# STM32F1_CNC_SCHB.net
KiCad netlist of a schematic drawn in Altium Designer
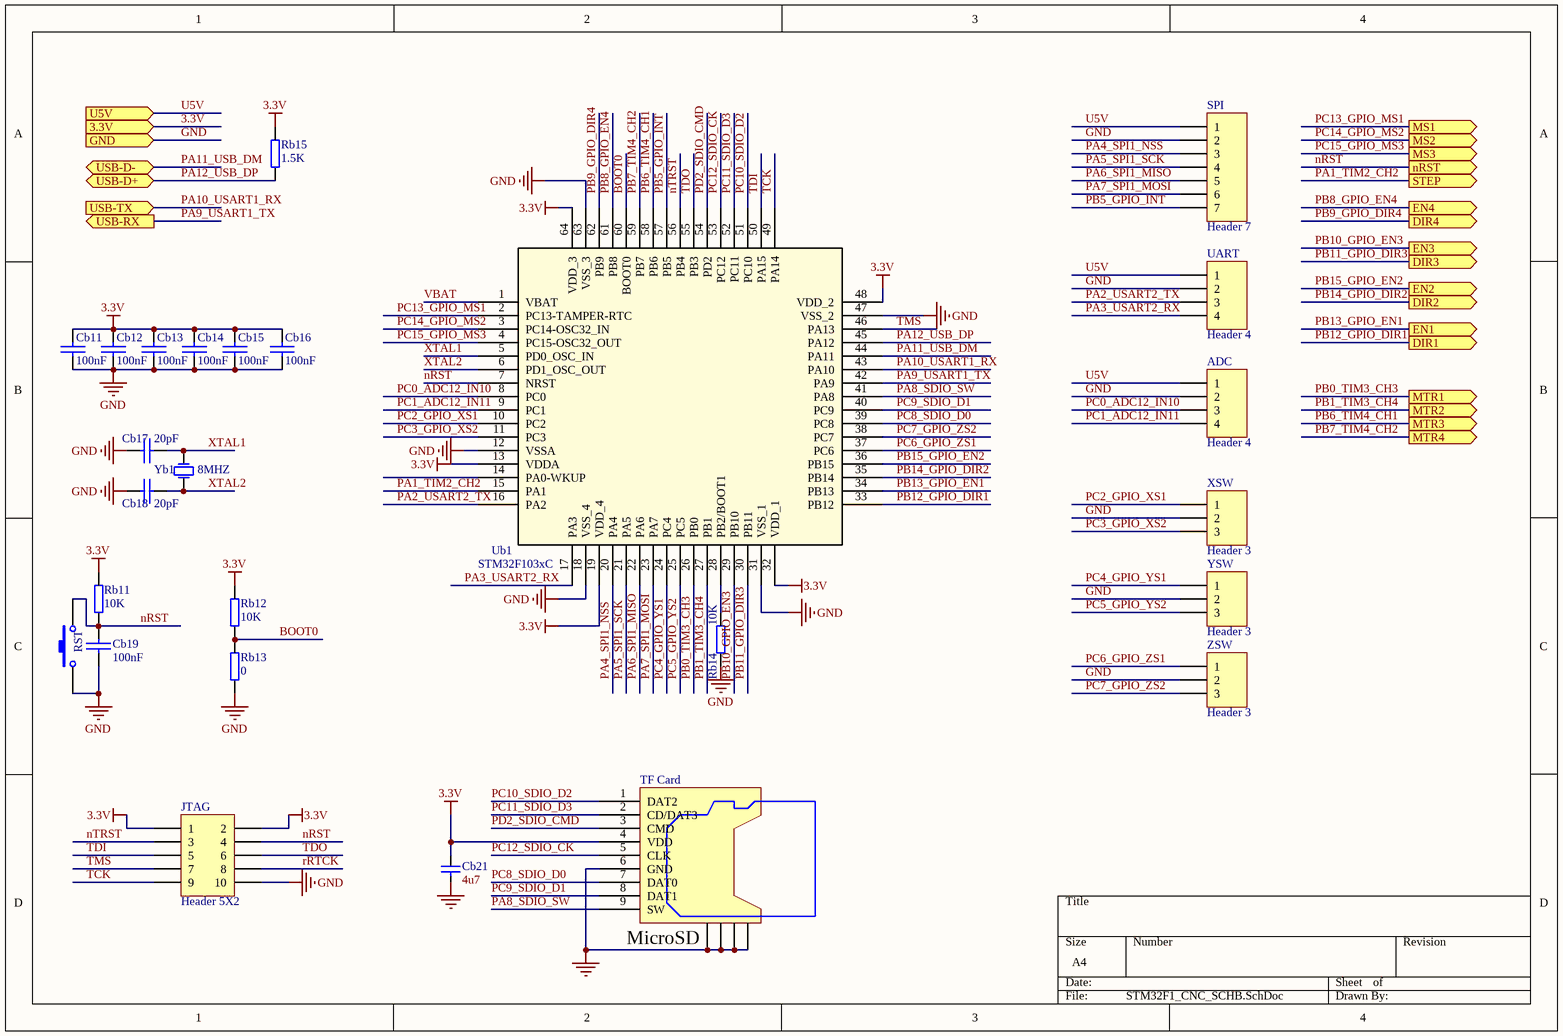
[diagram p0: STM32F1_CNC_SCHB.SchDoc]

(export (version "E")
  (design (tool "Eeschema 10.0.6"))
  (components
    (comp (ref "ADC")
      (value "Header 4")
      (footprint "HDR-2.54-4P")
      (description "Header, 4-Pin")
      (fields (field (name "PUBLISHER") "Altium Limited"))
      (libsource (lib "Miscellaneous Connectors") (part "Header 4"))
    )
    (comp (ref "Cb11")
      (value "100nF")
      (footprint "0603")
      (description "Capacitor")
      (libsource (lib "WEDOLIB") (part "CAP"))
    )
    (comp (ref "Cb12")
      (value "100nF")
      (footprint "0603")
      (description "Capacitor")
      (libsource (lib "WEDOLIB") (part "CAP"))
    )
    (comp (ref "Cb13")
      (value "100nF")
      (footprint "0603")
      (description "Capacitor")
      (libsource (lib "WEDOLIB") (part "CAP"))
    )
    (comp (ref "Cb14")
      (value "100nF")
      (footprint "0603")
      (description "Capacitor")
      (libsource (lib "WEDOLIB") (part "CAP"))
    )
    (comp (ref "Cb15")
      (value "100nF")
      (footprint "0603")
      (description "Capacitor")
      (libsource (lib "WEDOLIB") (part "CAP"))
    )
    (comp (ref "Cb16")
      (value "100nF")
      (footprint "0603")
      (description "Capacitor")
      (libsource (lib "WEDOLIB") (part "CAP"))
    )
    (comp (ref "Cb17")
      (value "20pF")
      (footprint "0603")
      (description "Capacitor")
      (libsource (lib "wedolib") (part "CAP"))
    )
    (comp (ref "Cb18")
      (value "20pF")
      (footprint "0603")
      (description "Capacitor")
      (libsource (lib "wedolib") (part "CAP"))
    )
    (comp (ref "Cb19")
      (value "100nF")
      (footprint "0603")
      (description "Capacitor")
      (libsource (lib "wedolib") (part "CAP"))
    )
    (comp (ref "Cb21") (value "4u7") (footprint "0603") (libsource (lib "s_device") (part "Cap")))
    (comp (ref "JTAG")
      (value "Header 5X2")
      (footprint "IDC10P-2.54")
      (description "Header, 5-Pin, Dual row")
      (fields (field (name "PUBLISHER") "Altium Limited"))
      (libsource (lib "Miscellaneous Connectors") (part "Header 5X2"))
    )
    (comp (ref "Rb11")
      (value "10K")
      (footprint "0603")
      (description "Resister")
      (libsource (lib "wedolib") (part "RES1"))
    )
    (comp (ref "Rb12")
      (value "10K")
      (footprint "0603")
      (description "Resister")
      (libsource (lib "WEDOLIB") (part "RES1"))
    )
    (comp (ref "Rb13")
      (value "0")
      (footprint "0603")
      (description "Resister")
      (libsource (lib "WEDOLIB") (part "RES1"))
    )
    (comp (ref "Rb14")
      (value "10K")
      (footprint "0603")
      (description "Resister")
      (libsource (lib "WEDOLIB") (part "RES1"))
    )
    (comp (ref "Rb15")
      (value "1.5K")
      (footprint "0603")
      (description "Resister")
      (libsource (lib "wedolib") (part "RES1"))
    )
    (comp (ref "RST")
      (value "SW-PB")
      (footprint "RST-6*6")
      (description "Switch")
      (fields (field (name "PUBLISHER") "Altium Limited"))
      (libsource (lib "Miscellaneous Devices") (part "SW-PB"))
    )
    (comp (ref "SPI")
      (value "Header 7")
      (footprint "HDR-2.54-7P")
      (description "Header, 7-Pin")
      (fields (field (name "PUBLISHER") "Altium Limited"))
      (libsource (lib "Miscellaneous Connectors") (part "Header 7"))
    )
    (comp (ref "TF Card")
      (value "microSD PUSH-PULL")
      (footprint "TF Card")
      (libsource (lib "pyboard") (part "microSD PUSH-PULL"))
    )
    (comp (ref "UART")
      (value "Header 4")
      (footprint "HDR-2.54-4P")
      (description "Header, 4-Pin")
      (fields (field (name "PUBLISHER") "Altium Limited"))
      (libsource (lib "Miscellaneous Connectors") (part "Header 4"))
    )
    (comp (ref "Ub1")
      (value "STM32F103xC")
      (footprint "QFP64")
      (libsource (lib "STM32F103xC") (part "STM32F103xC"))
    )
    (comp (ref "XSW")
      (value "Header 3")
      (footprint "HDR-2.54-3P")
      (description "Header, 3-Pin")
      (fields (field (name "PUBLISHER") "Altium Limited"))
      (libsource (lib "Miscellaneous Connectors") (part "Header 3"))
    )
    (comp (ref "Yb1")
      (value "8MHZ")
      (footprint "XTAL-3215-2P")
      (description "Crystal Oscillator")
      (fields (field (name "PUBLISHER") "Altium Limited"))
      (libsource (lib "*") (part "ECS-10-13-1"))
    )
    (comp (ref "YSW")
      (value "Header 3")
      (footprint "HDR-2.54-3P")
      (description "Header, 3-Pin")
      (fields (field (name "PUBLISHER") "Altium Limited"))
      (libsource (lib "Miscellaneous Connectors") (part "Header 3"))
    )
    (comp (ref "ZSW")
      (value "Header 3")
      (footprint "HDR-2.54-3P")
      (description "Header, 3-Pin")
      (fields (field (name "PUBLISHER") "Altium Limited"))
      (libsource (lib "Miscellaneous Connectors") (part "Header 3"))
    )
  )
  (nets
    (net (code "1") (name "/BOOT0") (class "Default")
      (node (ref "Rb12") (pin "2") (pinfunction "2_2") (pintype "passive"))
      (node (ref "Rb13") (pin "1") (pinfunction "1_1") (pintype "passive"))
      (node (ref "Ub1") (pin "60") (pinfunction "BOOT0_60") (pintype "passive"))
    )
    (net (code "2") (name "/PA1_TIM2_CH2") (class "Default")
      (node (ref "Ub1") (pin "15") (pinfunction "PA1_15") (pintype "passive"))
    )
    (net (code "3") (name "/PA2_USART2_TX") (class "Default")
      (node (ref "UART") (pin "3") (pinfunction "3_3") (pintype "passive"))
      (node (ref "Ub1") (pin "16") (pinfunction "PA2_16") (pintype "passive"))
    )
    (net (code "4") (name "/PA3_USART2_RX") (class "Default")
      (node (ref "UART") (pin "4") (pinfunction "4_4") (pintype "passive"))
      (node (ref "Ub1") (pin "17") (pinfunction "PA3_17") (pintype "passive"))
    )
    (net (code "5") (name "/PA4_SPI1_NSS") (class "Default")
      (node (ref "SPI") (pin "3") (pinfunction "3_3") (pintype "passive"))
      (node (ref "Ub1") (pin "20") (pinfunction "PA4_20") (pintype "passive"))
    )
    (net (code "6") (name "/PA5_SPI1_SCK") (class "Default")
      (node (ref "SPI") (pin "4") (pinfunction "4_4") (pintype "passive"))
      (node (ref "Ub1") (pin "21") (pinfunction "PA5_21") (pintype "passive"))
    )
    (net (code "7") (name "/PA6_SPI1_MISO") (class "Default")
      (node (ref "SPI") (pin "5") (pinfunction "5_5") (pintype "passive"))
      (node (ref "Ub1") (pin "22") (pinfunction "PA6_22") (pintype "passive"))
    )
    (net (code "8") (name "/PA7_SPI1_MOSI") (class "Default")
      (node (ref "SPI") (pin "6") (pinfunction "6_6") (pintype "passive"))
      (node (ref "Ub1") (pin "23") (pinfunction "PA7_23") (pintype "passive"))
    )
    (net (code "9") (name "/PA8_SDIO_SW") (class "Default")
      (node (ref "TF Card") (pin "9") (pinfunction "SW_9") (pintype "passive"))
      (node (ref "Ub1") (pin "41") (pinfunction "PA8_41") (pintype "passive"))
    )
    (net (code "10") (name "/PA9_USART1_TX") (class "Default")
      (node (ref "Ub1") (pin "42") (pinfunction "PA9_42") (pintype "passive"))
    )
    (net (code "11") (name "/PA10_USART1_RX") (class "Default")
      (node (ref "Ub1") (pin "43") (pinfunction "PA10_43") (pintype "passive"))
    )
    (net (code "12") (name "/PA11_USB_DM") (class "Default")
      (node (ref "Ub1") (pin "44") (pinfunction "PA11_44") (pintype "passive"))
    )
    (net (code "13") (name "/PA12_USB_DP") (class "Default")
      (node (ref "Rb15") (pin "2") (pinfunction "2_2") (pintype "passive"))
      (node (ref "Ub1") (pin "45") (pinfunction "PA12_45") (pintype "passive"))
    )
    (net (code "14") (name "/PB0_TIM3_CH3") (class "Default")
      (node (ref "Ub1") (pin "26") (pinfunction "PB0_26") (pintype "passive"))
    )
    (net (code "15") (name "/PB1_TIM3_CH4") (class "Default")
      (node (ref "Ub1") (pin "27") (pinfunction "PB1_27") (pintype "passive"))
    )
    (net (code "16") (name "/PB5_GPIO_INT") (class "Default")
      (node (ref "SPI") (pin "7") (pinfunction "7_7") (pintype "passive"))
      (node (ref "Ub1") (pin "57") (pinfunction "PB5_57") (pintype "passive"))
    )
    (net (code "17") (name "/PB6_TIM4_CH1") (class "Default")
      (node (ref "Ub1") (pin "58") (pinfunction "PB6_58") (pintype "passive"))
    )
    (net (code "18") (name "/PB7_TIM4_CH2") (class "Default")
      (node (ref "Ub1") (pin "59") (pinfunction "PB7_59") (pintype "passive"))
    )
    (net (code "19") (name "/PB8_GPIO_EN4") (class "Default")
      (node (ref "Ub1") (pin "61") (pinfunction "PB8_61") (pintype "passive"))
    )
    (net (code "20") (name "/PB9_GPIO_DIR4") (class "Default")
      (node (ref "Ub1") (pin "62") (pinfunction "PB9_62") (pintype "passive"))
    )
    (net (code "21") (name "/PB10_GPIO_EN3") (class "Default")
      (node (ref "Ub1") (pin "29") (pinfunction "PB10_29") (pintype "passive"))
    )
    (net (code "22") (name "/PB11_GPIO_DIR3") (class "Default")
      (node (ref "Ub1") (pin "30") (pinfunction "PB11_30") (pintype "passive"))
    )
    (net (code "23") (name "/PB12_GPIO_DIR1") (class "Default")
      (node (ref "Ub1") (pin "33") (pinfunction "PB12_33") (pintype "passive"))
    )
    (net (code "24") (name "/PB13_GPIO_EN1") (class "Default")
      (node (ref "Ub1") (pin "34") (pinfunction "PB13_34") (pintype "passive"))
    )
    (net (code "25") (name "/PB14_GPIO_DIR2") (class "Default")
      (node (ref "Ub1") (pin "35") (pinfunction "PB14_35") (pintype "passive"))
    )
    (net (code "26") (name "/PB15_GPIO_EN2") (class "Default")
      (node (ref "Ub1") (pin "36") (pinfunction "PB15_36") (pintype "passive"))
    )
    (net (code "27") (name "/PC0_ADC12_IN10") (class "Default")
      (node (ref "ADC") (pin "3") (pinfunction "3_3") (pintype "passive"))
      (node (ref "Ub1") (pin "8") (pinfunction "PC0_8") (pintype "passive"))
    )
    (net (code "28") (name "/PC1_ADC12_IN11") (class "Default")
      (node (ref "ADC") (pin "4") (pinfunction "4_4") (pintype "passive"))
      (node (ref "Ub1") (pin "9") (pinfunction "PC1_9") (pintype "passive"))
    )
    (net (code "29") (name "/PC2_GPIO_XS1") (class "Default")
      (node (ref "Ub1") (pin "10") (pinfunction "PC2_10") (pintype "passive"))
      (node (ref "XSW") (pin "1") (pinfunction "1_1") (pintype "passive"))
    )
    (net (code "30") (name "/PC3_GPIO_XS2") (class "Default")
      (node (ref "Ub1") (pin "11") (pinfunction "PC3_11") (pintype "passive"))
      (node (ref "XSW") (pin "3") (pinfunction "3_3") (pintype "passive"))
    )
    (net (code "31") (name "/PC4_GPIO_YS1") (class "Default")
      (node (ref "Ub1") (pin "24") (pinfunction "PC4_24") (pintype "passive"))
      (node (ref "YSW") (pin "1") (pinfunction "1_1") (pintype "passive"))
    )
    (net (code "32") (name "/PC5_GPIO_YS2") (class "Default")
      (node (ref "Ub1") (pin "25") (pinfunction "PC5_25") (pintype "passive"))
      (node (ref "YSW") (pin "3") (pinfunction "3_3") (pintype "passive"))
    )
    (net (code "33") (name "/PC6_GPIO_ZS1") (class "Default")
      (node (ref "Ub1") (pin "37") (pinfunction "PC6_37") (pintype "passive"))
      (node (ref "ZSW") (pin "1") (pinfunction "1_1") (pintype "passive"))
    )
    (net (code "34") (name "/PC7_GPIO_ZS2") (class "Default")
      (node (ref "Ub1") (pin "38") (pinfunction "PC7_38") (pintype "passive"))
      (node (ref "ZSW") (pin "3") (pinfunction "3_3") (pintype "passive"))
    )
    (net (code "35") (name "/PC8_SDIO_D0") (class "Default")
      (node (ref "TF Card") (pin "7") (pinfunction "DAT0_7") (pintype "passive"))
      (node (ref "Ub1") (pin "39") (pinfunction "PC8_39") (pintype "passive"))
    )
    (net (code "36") (name "/PC9_SDIO_D1") (class "Default")
      (node (ref "TF Card") (pin "8") (pinfunction "DAT1_8") (pintype "passive"))
      (node (ref "Ub1") (pin "40") (pinfunction "PC9_40") (pintype "passive"))
    )
    (net (code "37") (name "/PC10_SDIO_D2") (class "Default")
      (node (ref "TF Card") (pin "1") (pinfunction "DAT2_1") (pintype "passive"))
      (node (ref "Ub1") (pin "51") (pinfunction "PC10_51") (pintype "passive"))
    )
    (net (code "38") (name "/PC11_SDIO_D3") (class "Default")
      (node (ref "TF Card") (pin "2") (pinfunction "CD/DAT3_2") (pintype "passive"))
      (node (ref "Ub1") (pin "52") (pinfunction "PC11_52") (pintype "passive"))
    )
    (net (code "39") (name "/PC12_SDIO_CK") (class "Default")
      (node (ref "TF Card") (pin "5") (pinfunction "CLK_5") (pintype "passive"))
      (node (ref "Ub1") (pin "53") (pinfunction "PC12_53") (pintype "passive"))
    )
    (net (code "40") (name "/PC13_GPIO_MS1") (class "Default")
      (node (ref "Ub1") (pin "2") (pinfunction "PC13-TAMPER-RTC_2") (pintype "passive"))
    )
    (net (code "41") (name "/PC14_GPIO_MS2") (class "Default")
      (node (ref "Ub1") (pin "3") (pinfunction "PC14-OSC32_IN_3") (pintype "passive"))
    )
    (net (code "42") (name "/PC15_GPIO_MS3") (class "Default")
      (node (ref "Ub1") (pin "4") (pinfunction "PC15-OSC32_OUT_4") (pintype "passive"))
    )
    (net (code "43") (name "/PD2_SDIO_CMD") (class "Default")
      (node (ref "TF Card") (pin "3") (pinfunction "CMD_3") (pintype "passive"))
      (node (ref "Ub1") (pin "54") (pinfunction "PD2_54") (pintype "passive"))
    )
    (net (code "44") (name "/TCK") (class "Default")
      (node (ref "JTAG") (pin "9") (pinfunction "9_9") (pintype "passive"))
      (node (ref "Ub1") (pin "49") (pinfunction "PA14_49") (pintype "passive"))
    )
    (net (code "45") (name "/TDI") (class "Default")
      (node (ref "JTAG") (pin "5") (pinfunction "5_5") (pintype "passive"))
      (node (ref "Ub1") (pin "50") (pinfunction "PA15_50") (pintype "passive"))
    )
    (net (code "46") (name "/TDO") (class "Default")
      (node (ref "JTAG") (pin "6") (pinfunction "6_6") (pintype "passive"))
      (node (ref "Ub1") (pin "55") (pinfunction "PB3_55") (pintype "passive"))
    )
    (net (code "47") (name "/TMS") (class "Default")
      (node (ref "JTAG") (pin "7") (pinfunction "7_7") (pintype "passive"))
      (node (ref "Ub1") (pin "46") (pinfunction "PA13_46") (pintype "passive"))
    )
    (net (code "48") (name "/U5V") (class "Default")
      (node (ref "ADC") (pin "1") (pinfunction "1_1") (pintype "passive"))
      (node (ref "SPI") (pin "1") (pinfunction "1_1") (pintype "passive"))
      (node (ref "UART") (pin "1") (pinfunction "1_1") (pintype "passive"))
    )
    (net (code "49") (name "/VBAT") (class "Default")
      (node (ref "Ub1") (pin "1") (pinfunction "VBAT_1") (pintype "passive"))
    )
    (net (code "50") (name "/XTAL1") (class "Default")
      (node (ref "Cb17") (pin "2") (pinfunction "2_2") (pintype "passive"))
      (node (ref "Ub1") (pin "5") (pinfunction "PD0_OSC_IN_5") (pintype "passive"))
      (node (ref "Yb1") (pin "2") (pinfunction "OSC2_2") (pintype "passive"))
    )
    (net (code "51") (name "/XTAL2") (class "Default")
      (node (ref "Cb18") (pin "2") (pinfunction "2_2") (pintype "passive"))
      (node (ref "Ub1") (pin "6") (pinfunction "PD1_OSC_OUT_6") (pintype "passive"))
      (node (ref "Yb1") (pin "1") (pinfunction "OSC1_1") (pintype "passive"))
    )
    (net (code "52") (name "/nRST") (class "Default")
      (node (ref "Cb19") (pin "1") (pinfunction "1_1") (pintype "passive"))
      (node (ref "JTAG") (pin "4") (pinfunction "4_4") (pintype "passive"))
      (node (ref "RST") (pin "1") (pinfunction "1_1") (pintype "passive"))
      (node (ref "Rb11") (pin "2") (pinfunction "2_2") (pintype "passive"))
      (node (ref "Ub1") (pin "7") (pinfunction "NRST_7") (pintype "passive"))
    )
    (net (code "53") (name "/nTRST") (class "Default")
      (node (ref "JTAG") (pin "3") (pinfunction "3_3") (pintype "passive"))
      (node (ref "Ub1") (pin "56") (pinfunction "PB4_56") (pintype "passive"))
    )
    (net (code "54") (name "/rRTCK") (class "Default")
      (node (ref "JTAG") (pin "8") (pinfunction "8_8") (pintype "passive"))
    )
    (net (code "55") (name "3.3V") (class "Default")
      (node (ref "Cb11") (pin "1") (pinfunction "1_1") (pintype "passive"))
      (node (ref "Cb12") (pin "1") (pinfunction "1_1") (pintype "passive"))
      (node (ref "Cb13") (pin "1") (pinfunction "1_1") (pintype "passive"))
      (node (ref "Cb14") (pin "1") (pinfunction "1_1") (pintype "passive"))
      (node (ref "Cb15") (pin "1") (pinfunction "1_1") (pintype "passive"))
      (node (ref "Cb16") (pin "1") (pinfunction "1_1") (pintype "passive"))
      (node (ref "Cb21") (pin "2") (pintype "passive"))
      (node (ref "JTAG") (pin "1") (pinfunction "1_1") (pintype "passive"))
      (node (ref "JTAG") (pin "2") (pinfunction "2_2") (pintype "passive"))
      (node (ref "Rb11") (pin "1") (pinfunction "1_1") (pintype "passive"))
      (node (ref "Rb12") (pin "1") (pinfunction "1_1") (pintype "passive"))
      (node (ref "Rb15") (pin "1") (pinfunction "1_1") (pintype "passive"))
      (node (ref "TF Card") (pin "4") (pinfunction "VDD_4") (pintype "passive"))
      (node (ref "Ub1") (pin "13") (pinfunction "VDDA_13") (pintype "passive"))
      (node (ref "Ub1") (pin "19") (pinfunction "VDD_4_19") (pintype "passive"))
      (node (ref "Ub1") (pin "32") (pinfunction "VDD_1_32") (pintype "passive"))
      (node (ref "Ub1") (pin "48") (pinfunction "VDD_2_48") (pintype "passive"))
      (node (ref "Ub1") (pin "64") (pinfunction "VDD_3_64") (pintype "passive"))
    )
    (net (code "56") (name "GND") (class "Default")
      (node (ref "ADC") (pin "2") (pinfunction "2_2") (pintype "passive"))
      (node (ref "Cb11") (pin "2") (pinfunction "2_2") (pintype "passive"))
      (node (ref "Cb12") (pin "2") (pinfunction "2_2") (pintype "passive"))
      (node (ref "Cb13") (pin "2") (pinfunction "2_2") (pintype "passive"))
      (node (ref "Cb14") (pin "2") (pinfunction "2_2") (pintype "passive"))
      (node (ref "Cb15") (pin "2") (pinfunction "2_2") (pintype "passive"))
      (node (ref "Cb16") (pin "2") (pinfunction "2_2") (pintype "passive"))
      (node (ref "Cb17") (pin "1") (pinfunction "1_1") (pintype "passive"))
      (node (ref "Cb18") (pin "1") (pinfunction "1_1") (pintype "passive"))
      (node (ref "Cb19") (pin "2") (pinfunction "2_2") (pintype "passive"))
      (node (ref "Cb21") (pin "1") (pintype "passive"))
      (node (ref "JTAG") (pin "10") (pinfunction "10_10") (pintype "passive"))
      (node (ref "RST") (pin "2") (pinfunction "2_2") (pintype "passive"))
      (node (ref "Rb13") (pin "2") (pinfunction "2_2") (pintype "passive"))
      (node (ref "Rb14") (pin "2") (pinfunction "2_2") (pintype "passive"))
      (node (ref "SPI") (pin "2") (pinfunction "2_2") (pintype "passive"))
      (node (ref "TF Card") (pin "6") (pinfunction "GND_6") (pintype "passive"))
      (node (ref "TF Card") (pin "GP1") (pintype "passive"))
      (node (ref "TF Card") (pin "GP2") (pintype "passive"))
      (node (ref "TF Card") (pin "GP3") (pintype "passive"))
      (node (ref "TF Card") (pin "GP4") (pintype "passive"))
      (node (ref "UART") (pin "2") (pinfunction "2_2") (pintype "passive"))
      (node (ref "Ub1") (pin "12") (pinfunction "VSSA_12") (pintype "passive"))
      (node (ref "Ub1") (pin "18") (pinfunction "VSS_4_18") (pintype "passive"))
      (node (ref "Ub1") (pin "31") (pinfunction "VSS_1_31") (pintype "passive"))
      (node (ref "Ub1") (pin "47") (pinfunction "VSS_2_47") (pintype "passive"))
      (node (ref "Ub1") (pin "63") (pinfunction "VSS_3_63") (pintype "passive"))
      (node (ref "XSW") (pin "2") (pinfunction "2_2") (pintype "passive"))
      (node (ref "YSW") (pin "2") (pinfunction "2_2") (pintype "passive"))
      (node (ref "ZSW") (pin "2") (pinfunction "2_2") (pintype "passive"))
    )
    (net (code "57") (name "Net-(Ub1-PB2{slash}BOOT1)") (class "Default")
      (node (ref "Rb14") (pin "1") (pinfunction "1_1") (pintype "passive"))
      (node (ref "Ub1") (pin "28") (pinfunction "PB2/BOOT1_28") (pintype "passive"))
    )
    (net (code "58") (name "unconnected-(Ub1-PA0-WKUP-Pad14)") (class "Default")
      (node (ref "Ub1") (pin "14") (pinfunction "PA0-WKUP_14") (pintype "passive"))
    )
  )
)
